# V1_0.net
KiCad netlist of a schematic drawn in Altium Designer
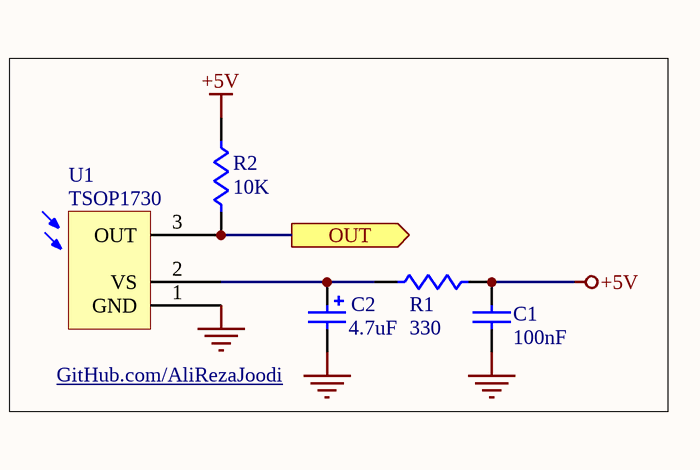
[diagram p0: V1.0.SchDoc]

(export (version "E")
  (design (tool "Eeschema 10.0.6"))
  (components
    (comp (ref "C1")
      (value "100nF")
      (footprint "CAPNTO2.54-3.05x1.78A")
      (description "Capacitor")
      (fields (field (name "MANUFACTURER") "Generic Components") (field (name "PUBLISHER") "Altium Limited"))
      (libsource (lib "Miscellaneous Devices") (part "Cap"))
    )
    (comp (ref "C2")
      (value "4.7uF")
      (footprint "CAPPR2.5-6.3x5")
      (description "Polarized Capacitor (Radial)")
      (fields (field (name "MANUFACTURER") "Generic Components") (field (name "PUBLISHER") "Altium Limited"))
      (libsource (lib "Miscellaneous Devices") (part "Cap Pol1"))
    )
    (comp (ref "R1")
      (value "330")
      (footprint "AXIAL-0.4")
      (description "Resistor")
      (fields (field (name "MANUFACTURER") "Generic Components") (field (name "PUBLISHER") "Altium Limited"))
      (libsource (lib "Miscellaneous Devices") (part "Res1"))
    )
    (comp (ref "R2")
      (value "10K")
      (footprint "AXIAL-0.4")
      (description "Resistor")
      (fields (field (name "MANUFACTURER") "Generic Components") (field (name "PUBLISHER") "Altium Limited"))
      (libsource (lib "Miscellaneous Devices") (part "Res1"))
    )
    (comp (ref "U1")
      (value "TSOP1730")
      (footprint "IR10")
      (description "IR receiver module for remote control")
      (libsource (lib "PicPars.com_usefully_Library") (part "IR Module"))
    )
  )
  (nets
    (net (code "1") (name "+5V") (class "Default")
      (node (ref "C1") (pin "2") (pinfunction "2_2") (pintype "passive"))
      (node (ref "R1") (pin "1") (pinfunction "1_1") (pintype "passive"))
      (node (ref "R2") (pin "1") (pinfunction "1_1") (pintype "passive"))
    )
    (net (code "2") (name "/OUT") (class "Default")
      (node (ref "R2") (pin "2") (pinfunction "2_2") (pintype "passive"))
      (node (ref "U1") (pin "3") (pinfunction "OUT_3") (pintype "passive"))
    )
    (net (code "3") (name "GND") (class "Default")
      (node (ref "C1") (pin "1") (pinfunction "1_1") (pintype "passive"))
      (node (ref "C2") (pin "2") (pinfunction "2_2") (pintype "passive"))
      (node (ref "U1") (pin "1") (pinfunction "GND_1") (pintype "passive"))
    )
    (net (code "4") (name "Net-(U1-VS)") (class "Default")
      (node (ref "C2") (pin "1") (pinfunction "1_1") (pintype "passive"))
      (node (ref "R1") (pin "2") (pinfunction "2_2") (pintype "passive"))
      (node (ref "U1") (pin "2") (pinfunction "VS_2") (pintype "passive"))
    )
  )
)
